# loaddump.net
KiCad netlist of a schematic drawn in EAGLE
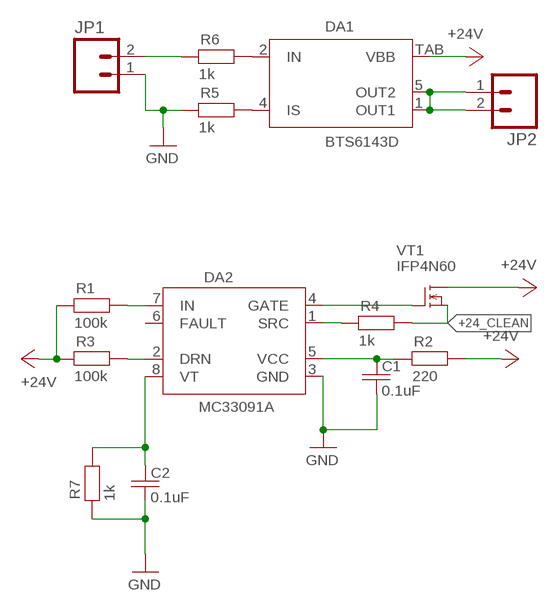
[diagram p0: schematic, sheet 1]

(export (version "E")
  (design (tool "Eeschema 10.0.6"))
  (components
    (comp (ref "C1")
      (value "0.1uF")
      (footprint "eagle-import:C0805")
      (libsource (lib "eagle-import") (part "C-EUC0805"))
    )
    (comp (ref "C2")
      (value "0.1uF")
      (footprint "eagle-import:C0805")
      (libsource (lib "eagle-import") (part "C-EUC0805"))
    )
    (comp (ref "DA1")
      (value "BTS6143D")
      (footprint "eagle-import:TO252-5-11")
      (libsource (lib "eagle-import") (part "BTS6143D"))
    )
    (comp (ref "DA2")
      (value "MC33091A")
      (footprint "eagle-import:SO08")
      (libsource (lib "eagle-import") (part "MC33091A"))
    )
    (comp (ref "JP1")
      (value "M02PTH3")
      (footprint "eagle-import:1X02_LONGPADS")
      (libsource (lib "eagle-import") (part "M02PTH3"))
    )
    (comp (ref "JP2")
      (value "M02PTH3")
      (footprint "eagle-import:1X02_LONGPADS")
      (libsource (lib "eagle-import") (part "M02PTH3"))
    )
    (comp (ref "R1")
      (value "100k")
      (footprint "eagle-import:R0805")
      (libsource (lib "eagle-import") (part "R-EU_R0805"))
    )
    (comp (ref "R2")
      (value "220")
      (footprint "eagle-import:0922_22")
      (libsource (lib "eagle-import") (part "R-EU_0922/22"))
    )
    (comp (ref "R3")
      (value "100k")
      (footprint "eagle-import:R0805")
      (libsource (lib "eagle-import") (part "R-EU_R0805"))
    )
    (comp (ref "R4")
      (value "1k")
      (footprint "eagle-import:R0805")
      (libsource (lib "eagle-import") (part "R-EU_R0805"))
    )
    (comp (ref "R5")
      (value "1k")
      (footprint "eagle-import:R0805")
      (libsource (lib "eagle-import") (part "R-EU_R0805"))
    )
    (comp (ref "R6")
      (value "1k")
      (footprint "eagle-import:R0805")
      (libsource (lib "eagle-import") (part "R-EU_R0805"))
    )
    (comp (ref "R7")
      (value "1k")
      (footprint "eagle-import:R0805")
      (libsource (lib "eagle-import") (part "R-EU_R0805"))
    )
    (comp (ref "VT1")
      (value "IFP4N60")
      (footprint "eagle-import:TO220")
      (libsource (lib "eagle-import") (part "IFP4N60"))
    )
  )
  (nets
    (net (code "1") (name "+24V") (class "Default")
      (node (ref "DA1") (pin "TAB") (pinfunction "VBB_TAB") (pintype "power_in"))
      (node (ref "R1") (pin "1") (pinfunction "1_1") (pintype "passive"))
      (node (ref "R2") (pin "2") (pinfunction "2_2") (pintype "passive"))
      (node (ref "R3") (pin "1") (pinfunction "1_1") (pintype "passive"))
      (node (ref "VT1") (pin "2") (pinfunction "D_2") (pintype "passive"))
    )
    (net (code "2") (name "+24_CLEAN") (class "Default")
      (node (ref "R4") (pin "2") (pinfunction "2_2") (pintype "passive"))
      (node (ref "VT1") (pin "3") (pinfunction "S_3") (pintype "passive"))
    )
    (net (code "3") (name "GND") (class "Default")
      (node (ref "C1") (pin "2") (pinfunction "2_2") (pintype "passive"))
      (node (ref "C2") (pin "2") (pinfunction "2_2") (pintype "passive"))
      (node (ref "DA2") (pin "3") (pinfunction "GND_3") (pintype "power_in"))
      (node (ref "JP1") (pin "1") (pinfunction "1_1") (pintype "passive"))
      (node (ref "R5") (pin "1") (pinfunction "1_1") (pintype "passive"))
      (node (ref "R7") (pin "1") (pinfunction "1_1") (pintype "passive"))
    )
    (net (code "4") (name "Net-(DA1-IN)") (class "Default")
      (node (ref "DA1") (pin "2") (pinfunction "IN_2") (pintype "input"))
      (node (ref "R6") (pin "2") (pinfunction "2_2") (pintype "passive"))
    )
    (net (code "5") (name "Net-(DA1-IS)") (class "Default")
      (node (ref "DA1") (pin "4") (pinfunction "IS_4") (pintype "output"))
      (node (ref "R5") (pin "2") (pinfunction "2_2") (pintype "passive"))
    )
    (net (code "6") (name "Net-(DA1-OUT1)") (class "Default")
      (node (ref "DA1") (pin "1") (pinfunction "OUT1_1") (pintype "power_in"))
      (node (ref "DA1") (pin "5") (pinfunction "OUT2_5") (pintype "power_in"))
      (node (ref "JP2") (pin "1") (pinfunction "1_1") (pintype "passive"))
      (node (ref "JP2") (pin "2") (pinfunction "2_2") (pintype "passive"))
    )
    (net (code "7") (name "Net-(DA2-DRN)") (class "Default")
      (node (ref "DA2") (pin "2") (pinfunction "DRN_2") (pintype "bidirectional"))
      (node (ref "R3") (pin "2") (pinfunction "2_2") (pintype "passive"))
    )
    (net (code "8") (name "Net-(DA2-GATE)") (class "Default")
      (node (ref "DA2") (pin "4") (pinfunction "GATE_4") (pintype "output"))
      (node (ref "VT1") (pin "1") (pinfunction "G_1") (pintype "passive"))
    )
    (net (code "9") (name "Net-(DA2-IN)") (class "Default")
      (node (ref "DA2") (pin "7") (pinfunction "IN_7") (pintype "input"))
      (node (ref "R1") (pin "2") (pinfunction "2_2") (pintype "passive"))
    )
    (net (code "10") (name "Net-(DA2-SRC)") (class "Default")
      (node (ref "DA2") (pin "1") (pinfunction "SRC_1") (pintype "bidirectional"))
      (node (ref "R4") (pin "1") (pinfunction "1_1") (pintype "passive"))
    )
    (net (code "11") (name "Net-(DA2-VCC)") (class "Default")
      (node (ref "C1") (pin "1") (pinfunction "1_1") (pintype "passive"))
      (node (ref "DA2") (pin "5") (pinfunction "VCC_5") (pintype "power_in"))
      (node (ref "R2") (pin "1") (pinfunction "1_1") (pintype "passive"))
    )
    (net (code "12") (name "Net-(DA2-VT)") (class "Default")
      (node (ref "C2") (pin "1") (pinfunction "1_1") (pintype "passive"))
      (node (ref "DA2") (pin "8") (pinfunction "VT_8") (pintype "bidirectional"))
      (node (ref "R7") (pin "2") (pinfunction "2_2") (pintype "passive"))
    )
    (net (code "13") (name "Net-(JP1-Pad2)") (class "Default")
      (node (ref "JP1") (pin "2") (pinfunction "2_2") (pintype "passive"))
      (node (ref "R6") (pin "1") (pinfunction "1_1") (pintype "passive"))
    )
    (net (code "14") (name "unconnected-(DA2-FAULT-Pad6)") (class "Default")
      (node (ref "DA2") (pin "6") (pinfunction "FAULT_6") (pintype "open_collector"))
    )
  )
)
